# OPA847_LNA.net
KiCad netlist of a schematic drawn in Altium Designer
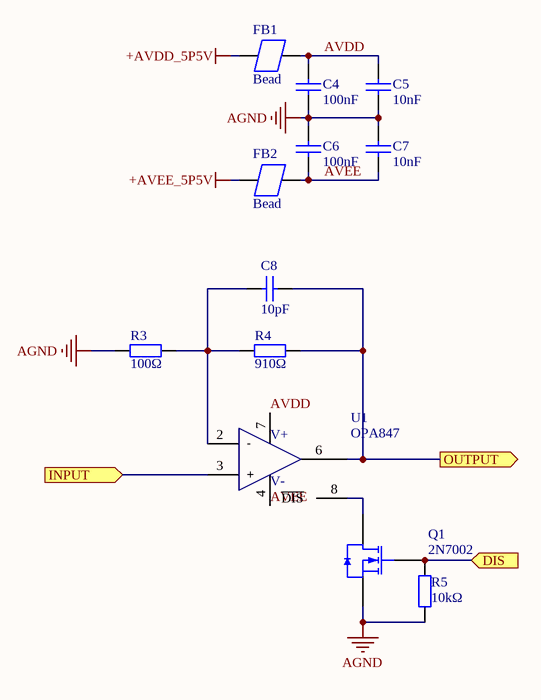
[diagram p0: OPA847_LNA.SchDoc]

(export (version "E")
  (design (tool "Eeschema 10.0.6"))
  (components
    (comp (ref "C4")
      (value "100nF")
      (footprint "0603_C")
      (description "贴片电容")
      (libsource (lib "Miscellaneous Devices LC") (part "0603 100nF (104) 10% 50V"))
    )
    (comp (ref "C5")
      (value "10nF")
      (footprint "0603_C")
      (description "贴片电容")
      (libsource (lib "Miscellaneous Devices LC") (part "0603 10nF (103) 10% 50V"))
    )
    (comp (ref "C6")
      (value "100nF")
      (footprint "0603_C")
      (description "贴片电容")
      (libsource (lib "Miscellaneous Devices LC") (part "0603 100nF (104) 10% 50V"))
    )
    (comp (ref "C7")
      (value "10nF")
      (footprint "0603_C")
      (description "贴片电容")
      (libsource (lib "Miscellaneous Devices LC") (part "0603 10nF (103) 10% 50V"))
    )
    (comp (ref "C8")
      (value "10pF")
      (footprint "0603_C")
      (description "贴片电容")
      (libsource (lib "Miscellaneous Devices LC") (part "0603 10pF (100) 5% 50V"))
    )
    (comp (ref "FB1") (value "Bead") (footprint "0805_L") (libsource (lib "OlvkLib") (part "Bead")))
    (comp (ref "FB2") (value "Bead") (footprint "0805_L") (libsource (lib "OlvkLib") (part "Bead")))
    (comp (ref "Q1")
      (value "2N7002")
      (footprint "SOT-23(SOT-23-3)")
      (description "MOS(场效应管)")
      (libsource (lib "Miscellaneous Devices LC") (part "2N7002 7002"))
    )
    (comp (ref "R3")
      (value "100Ω")
      (footprint "0603_R")
      (description "贴片电阻")
      (libsource (lib "Miscellaneous Devices LC") (part "0603 100Ω (1000) 1%"))
    )
    (comp (ref "R4")
      (value "910Ω")
      (footprint "0603_R")
      (description "贴片电阻")
      (libsource (lib "Miscellaneous Devices LC") (part "0603 910Ω (9100) 1%"))
    )
    (comp (ref "R5")
      (value "10kΩ")
      (footprint "0603_R")
      (description "贴片电阻")
      (libsource (lib "Miscellaneous Devices LC") (part "0603 10KΩ (1002) 1%"))
    )
    (comp (ref "U1")
      (value "OPA847")
      (footprint "SOIC127P600X175-8M")
      (description "Wideband, Ultra-Low Noise, Voltage-Feedback OPERATIONAL AMPLIFIER with Shutdown")
      (libsource (lib "OlvkLib") (part "OPA847"))
    )
  )
  (nets
    (net (code "1") (name "+AVDD_5P5V") (class "Default")
      (node (ref "FB1") (pin "1") (pinfunction "1_1") (pintype "passive"))
    )
    (net (code "2") (name "+AVEE_5P5V") (class "Default")
      (node (ref "FB2") (pin "1") (pinfunction "1_1") (pintype "passive"))
    )
    (net (code "3") (name "/AVDD") (class "Default")
      (node (ref "C4") (pin "2") (pinfunction "2_2") (pintype "passive"))
      (node (ref "C5") (pin "2") (pinfunction "2_2") (pintype "passive"))
      (node (ref "FB1") (pin "2") (pinfunction "2_2") (pintype "passive"))
      (node (ref "U1") (pin "7") (pinfunction "VCC+_7") (pintype "passive"))
    )
    (net (code "4") (name "/AVEE") (class "Default")
      (node (ref "C6") (pin "2") (pinfunction "2_2") (pintype "passive"))
      (node (ref "C7") (pin "2") (pinfunction "2_2") (pintype "passive"))
      (node (ref "FB2") (pin "2") (pinfunction "2_2") (pintype "passive"))
      (node (ref "U1") (pin "4") (pinfunction "VCC-_4") (pintype "passive"))
    )
    (net (code "5") (name "/DIS") (class "Default")
      (node (ref "Q1") (pin "1") (pinfunction "G_1") (pintype "passive"))
      (node (ref "R5") (pin "2") (pinfunction "2_2") (pintype "passive"))
    )
    (net (code "6") (name "/INPUT") (class "Default")
      (node (ref "U1") (pin "3") (pinfunction "3_3") (pintype "passive"))
    )
    (net (code "7") (name "/OUTPUT") (class "Default")
      (node (ref "C8") (pin "2") (pinfunction "2_2") (pintype "passive"))
      (node (ref "R4") (pin "2") (pinfunction "2_2") (pintype "passive"))
      (node (ref "U1") (pin "6") (pinfunction "1_6") (pintype "passive"))
    )
    (net (code "8") (name "AGND") (class "Default")
      (node (ref "C4") (pin "1") (pinfunction "1_1") (pintype "passive"))
      (node (ref "C5") (pin "1") (pinfunction "1_1") (pintype "passive"))
      (node (ref "C6") (pin "1") (pinfunction "1_1") (pintype "passive"))
      (node (ref "C7") (pin "1") (pinfunction "1_1") (pintype "passive"))
      (node (ref "Q1") (pin "2") (pinfunction "S_2") (pintype "passive"))
      (node (ref "R3") (pin "1") (pinfunction "1_1") (pintype "passive"))
      (node (ref "R5") (pin "1") (pinfunction "1_1") (pintype "passive"))
    )
    (net (code "9") (name "Net-(C8-Pad1)") (class "Default")
      (node (ref "C8") (pin "1") (pinfunction "1_1") (pintype "passive"))
      (node (ref "R3") (pin "2") (pinfunction "2_2") (pintype "passive"))
      (node (ref "R4") (pin "1") (pinfunction "1_1") (pintype "passive"))
      (node (ref "U1") (pin "2") (pinfunction "2_2") (pintype "passive"))
    )
    (net (code "10") (name "Net-(Q1-D)") (class "Default")
      (node (ref "Q1") (pin "3") (pinfunction "D_3") (pintype "passive"))
      (node (ref "U1") (pin "8") (pinfunction "~{DIS}_8") (pintype "passive"))
    )
  )
)
